# eeprom_arduino.net
KiCad netlist of a schematic drawn in EAGLE
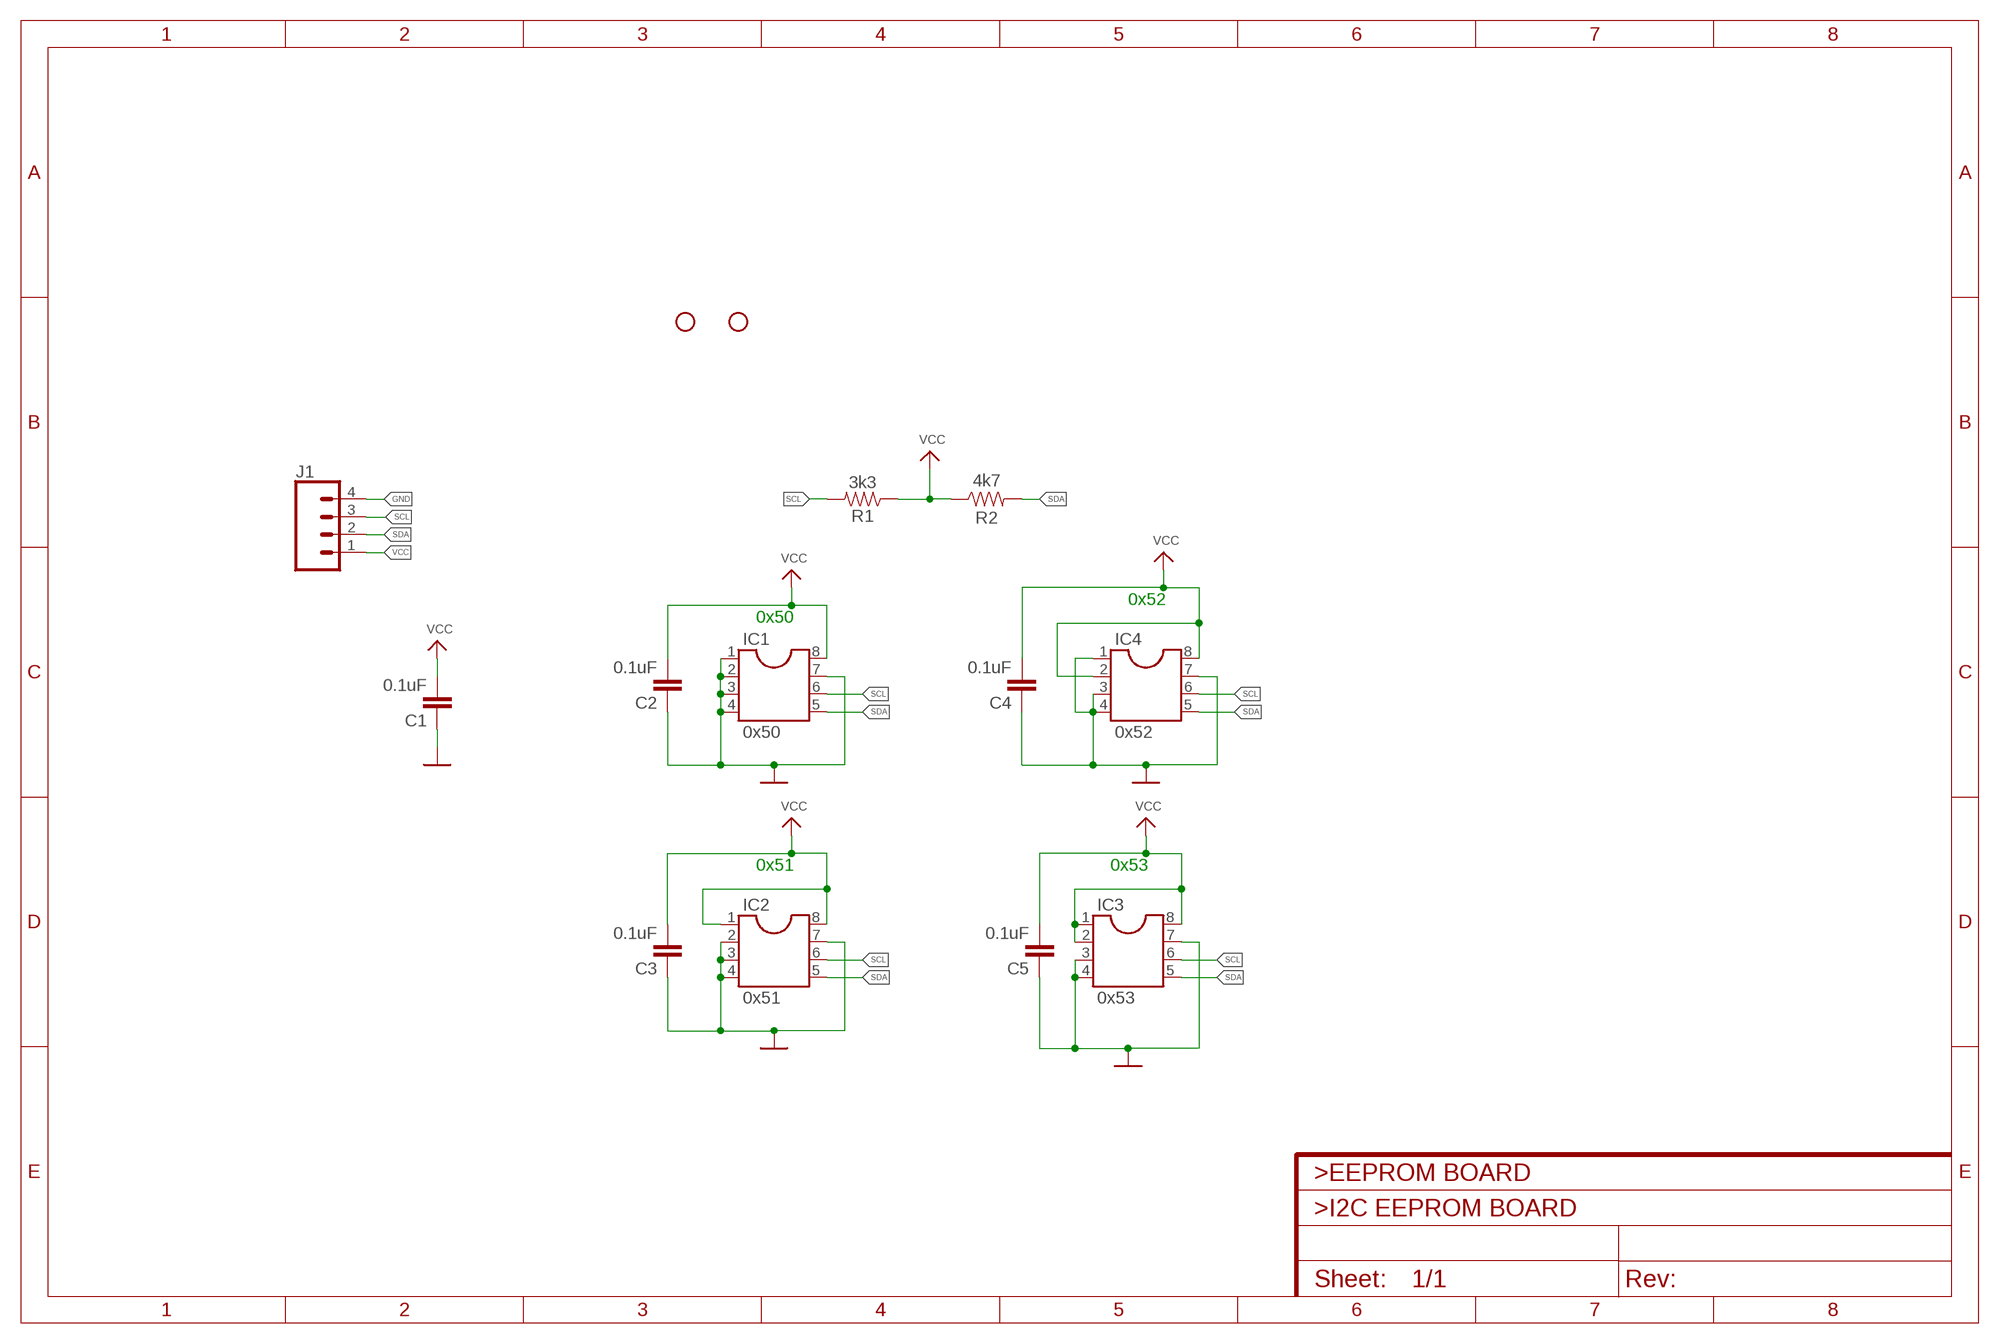
[diagram p0: schematic, sheet 1]

(export (version "E")
  (design (tool "Eeschema 10.0.6"))
  (components
    (comp (ref "C1")
      (value "0.1uF")
      (footprint "eagle-import:CAP-PTH-SMALL-KIT")
      (libsource (lib "eagle-import") (part "0.1UF-KIT-EZ-50V-20%"))
    )
    (comp (ref "C2")
      (value "0.1uF")
      (footprint "eagle-import:CAP-PTH-SMALL-KIT")
      (libsource (lib "eagle-import") (part "0.1UF-KIT-EZ-50V-20%"))
    )
    (comp (ref "C3")
      (value "0.1uF")
      (footprint "eagle-import:CAP-PTH-SMALL-KIT")
      (libsource (lib "eagle-import") (part "0.1UF-KIT-EZ-50V-20%"))
    )
    (comp (ref "C4")
      (value "0.1uF")
      (footprint "eagle-import:CAP-PTH-SMALL-KIT")
      (libsource (lib "eagle-import") (part "0.1UF-KIT-EZ-50V-20%"))
    )
    (comp (ref "C5")
      (value "0.1uF")
      (footprint "eagle-import:CAP-PTH-SMALL-KIT")
      (libsource (lib "eagle-import") (part "0.1UF-KIT-EZ-50V-20%"))
    )
    (comp (ref "H1")
      (value "STAND-OFF")
      (footprint "eagle-import:STAND-OFF")
      (libsource (lib "eagle-import") (part "STAND-OFF"))
    )
    (comp (ref "H2")
      (value "STAND-OFF")
      (footprint "eagle-import:STAND-OFF")
      (libsource (lib "eagle-import") (part "STAND-OFF"))
    )
    (comp (ref "IC1")
      (value "0x50")
      (footprint "eagle-import:SOCKET-08")
      (libsource (lib "eagle-import") (part "DIL8S"))
    )
    (comp (ref "IC2")
      (value "0x51")
      (footprint "eagle-import:SOCKET-08")
      (libsource (lib "eagle-import") (part "DIL8S"))
    )
    (comp (ref "IC3")
      (value "0x53")
      (footprint "eagle-import:SOCKET-08")
      (libsource (lib "eagle-import") (part "DIL8S"))
    )
    (comp (ref "IC4")
      (value "0x52")
      (footprint "eagle-import:SOCKET-08")
      (libsource (lib "eagle-import") (part "DIL8S"))
    )
    (comp (ref "J1")
      (value "CONN_04POLAR")
      (footprint "eagle-import:MOLEX-1X4")
      (libsource (lib "eagle-import") (part "CONN_04POLAR"))
    )
    (comp (ref "R1")
      (value "3k3")
      (footprint "eagle-import:AXIAL-0.3")
      (libsource (lib "eagle-import") (part "10KOHM-HORIZ-1/4W-1%"))
    )
    (comp (ref "R2")
      (value "4k7")
      (footprint "eagle-import:AXIAL-0.3")
      (libsource (lib "eagle-import") (part "10KOHM-HORIZ-1/4W-1%"))
    )
  )
  (nets
    (net (code "1") (name "GND") (class "Default")
      (node (ref "C1") (pin "1") (pinfunction "1_1") (pintype "passive"))
      (node (ref "C2") (pin "1") (pinfunction "1_1") (pintype "passive"))
      (node (ref "C3") (pin "1") (pinfunction "1_1") (pintype "passive"))
      (node (ref "C4") (pin "1") (pinfunction "1_1") (pintype "passive"))
      (node (ref "C5") (pin "1") (pinfunction "1_1") (pintype "passive"))
      (node (ref "IC1") (pin "1") (pinfunction "1_1") (pintype "passive"))
      (node (ref "IC1") (pin "2") (pinfunction "2_2") (pintype "passive"))
      (node (ref "IC1") (pin "3") (pinfunction "3_3") (pintype "passive"))
      (node (ref "IC1") (pin "4") (pinfunction "4_4") (pintype "passive"))
      (node (ref "IC1") (pin "7") (pinfunction "7_7") (pintype "passive"))
      (node (ref "IC2") (pin "2") (pinfunction "2_2") (pintype "passive"))
      (node (ref "IC2") (pin "3") (pinfunction "3_3") (pintype "passive"))
      (node (ref "IC2") (pin "4") (pinfunction "4_4") (pintype "passive"))
      (node (ref "IC2") (pin "7") (pinfunction "7_7") (pintype "passive"))
      (node (ref "IC3") (pin "3") (pinfunction "3_3") (pintype "passive"))
      (node (ref "IC3") (pin "4") (pinfunction "4_4") (pintype "passive"))
      (node (ref "IC3") (pin "7") (pinfunction "7_7") (pintype "passive"))
      (node (ref "IC4") (pin "1") (pinfunction "1_1") (pintype "passive"))
      (node (ref "IC4") (pin "3") (pinfunction "3_3") (pintype "passive"))
      (node (ref "IC4") (pin "4") (pinfunction "4_4") (pintype "passive"))
      (node (ref "IC4") (pin "7") (pinfunction "7_7") (pintype "passive"))
      (node (ref "J1") (pin "4") (pinfunction "4_4") (pintype "passive"))
    )
    (net (code "2") (name "SCL") (class "Default")
      (node (ref "IC1") (pin "6") (pinfunction "6_6") (pintype "passive"))
      (node (ref "IC2") (pin "6") (pinfunction "6_6") (pintype "passive"))
      (node (ref "IC3") (pin "6") (pinfunction "6_6") (pintype "passive"))
      (node (ref "IC4") (pin "6") (pinfunction "6_6") (pintype "passive"))
      (node (ref "J1") (pin "3") (pinfunction "3_3") (pintype "passive"))
      (node (ref "R1") (pin "P$2") (pinfunction "2_P$2") (pintype "passive"))
    )
    (net (code "3") (name "SDA") (class "Default")
      (node (ref "IC1") (pin "5") (pinfunction "5_5") (pintype "passive"))
      (node (ref "IC2") (pin "5") (pinfunction "5_5") (pintype "passive"))
      (node (ref "IC3") (pin "5") (pinfunction "5_5") (pintype "passive"))
      (node (ref "IC4") (pin "5") (pinfunction "5_5") (pintype "passive"))
      (node (ref "J1") (pin "2") (pinfunction "2_2") (pintype "passive"))
      (node (ref "R2") (pin "P$2") (pinfunction "2_P$2") (pintype "passive"))
    )
    (net (code "4") (name "VCC") (class "Default")
      (node (ref "C1") (pin "2") (pinfunction "2_2") (pintype "passive"))
      (node (ref "C2") (pin "2") (pinfunction "2_2") (pintype "passive"))
      (node (ref "C3") (pin "2") (pinfunction "2_2") (pintype "passive"))
      (node (ref "C4") (pin "2") (pinfunction "2_2") (pintype "passive"))
      (node (ref "C5") (pin "2") (pinfunction "2_2") (pintype "passive"))
      (node (ref "IC1") (pin "8") (pinfunction "8_8") (pintype "passive"))
      (node (ref "IC2") (pin "1") (pinfunction "1_1") (pintype "passive"))
      (node (ref "IC2") (pin "8") (pinfunction "8_8") (pintype "passive"))
      (node (ref "IC3") (pin "1") (pinfunction "1_1") (pintype "passive"))
      (node (ref "IC3") (pin "2") (pinfunction "2_2") (pintype "passive"))
      (node (ref "IC3") (pin "8") (pinfunction "8_8") (pintype "passive"))
      (node (ref "IC4") (pin "2") (pinfunction "2_2") (pintype "passive"))
      (node (ref "IC4") (pin "8") (pinfunction "8_8") (pintype "passive"))
      (node (ref "J1") (pin "1") (pinfunction "1_1") (pintype "passive"))
      (node (ref "R1") (pin "P$1") (pinfunction "1_P$1") (pintype "passive"))
      (node (ref "R2") (pin "P$1") (pinfunction "1_P$1") (pintype "passive"))
    )
  )
)
